# 4_ETHERNET.net
KiCad netlist of a schematic drawn in Altium Designer
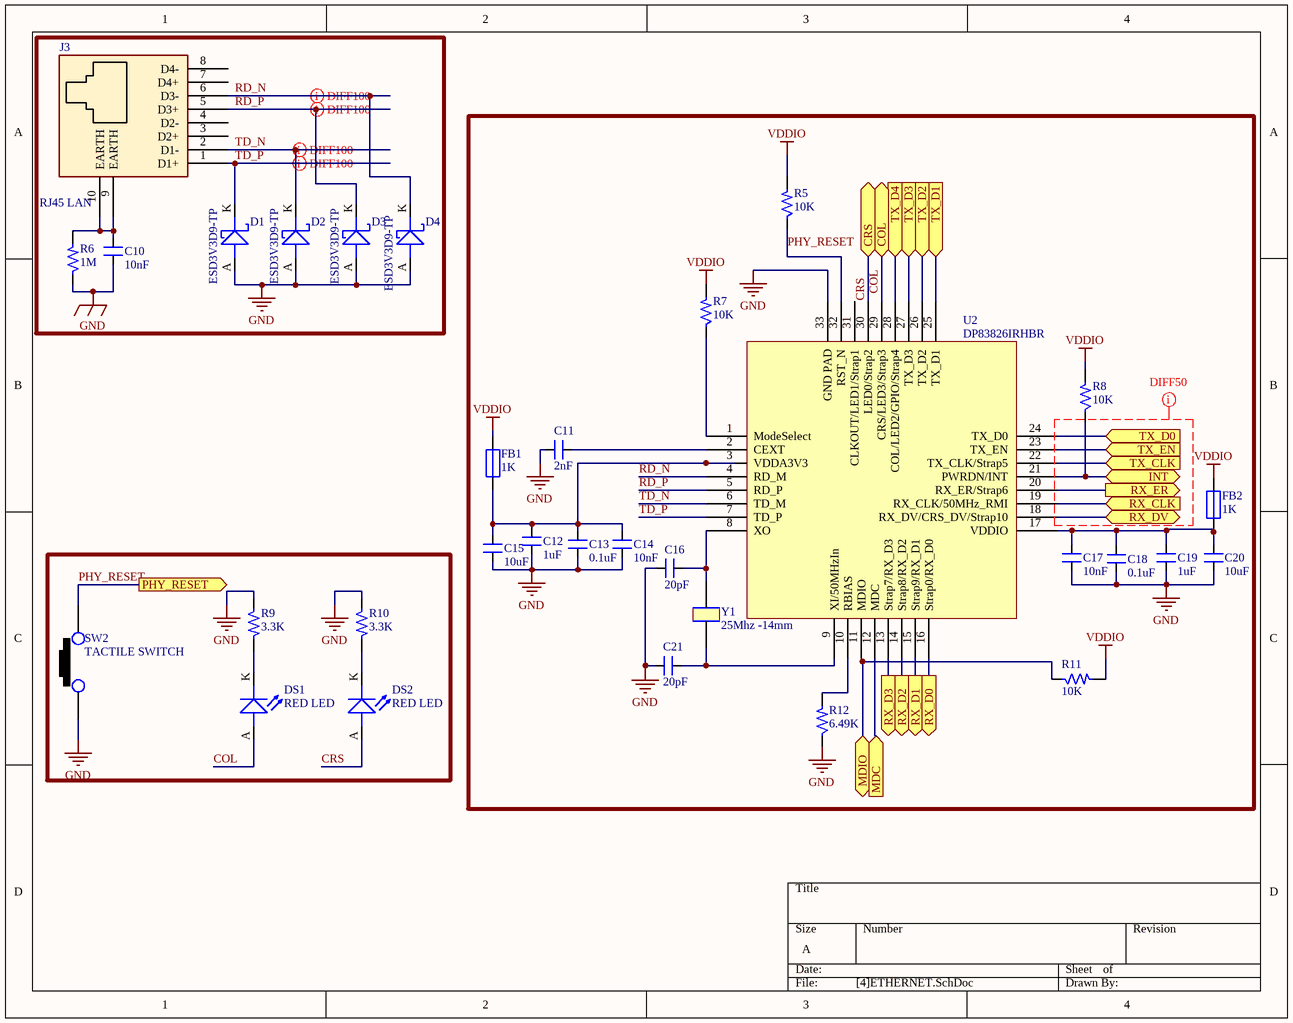
[diagram p0: [4]ETHERNET.SchDoc]

(export (version "E")
  (design (tool "Eeschema 10.0.6"))
  (components
    (comp (ref "C10")
      (value "10nF")
      (footprint "CAP_P196_102X287_H332_RAD_TH")
      (description "10000pF ±10% 1000V (1kV) Ceramic Capacitor X7R Radial")
      (fields
        (field (name "MANUFACTURER") "Yageo")
        (field (name "MANUFACTURER PART NUMBER") "RDER73A103K2K1H03B")
      )
      (libsource (lib "ESTEEMPCBLIB") (part "CAP_10nF-1KV-10%-RAD-TH"))
    )
    (comp (ref "C11")
      (value "2nF")
      (footprint "CAP_0805")
      (description "2000pF ±10% 50V Ceramic Capacitor X7R 0805 (2012 Metric)")
      (fields
        (field (name "MANUFACTURER") "Samsung Electro-Mechanics")
        (field (name "MANUFACTURER PART NUMBER") "CL21B202KBANNNC")
      )
      (libsource (lib "ESTEEMPCBLIB") (part "CAP_2nF-50V-10%-0805"))
    )
    (comp (ref "C12")
      (value "1uF")
      (footprint "CAP_0805")
      (description "1µF ±5% 50V Ceramic Capacitor X7R 0805 (2012 Metric)")
      (fields
        (field (name "MANUFACTURER") "Samsung")
        (field (name "MANUFACTURER PART NUMBER") "CC0805JKX7R9BB105")
      )
      (libsource (lib "ESTEEMPCBLIB") (part "CAP_1uF-50V-5%-0805"))
    )
    (comp (ref "C13")
      (value "0.1uF")
      (footprint "CAP_0805")
      (description "0.1µF ±10% 50V Ceramic Capacitor X7R 0805 (2012 Metric)")
      (fields
        (field (name "MANUFACTURER") "Samsung")
        (field (name "MANUFACTURER PART NUMBER") "CL21B104KBCNNNC")
      )
      (libsource (lib "ESTEEMPCBLIB") (part "CAP_0.1uF-50V-10%-0805"))
    )
    (comp (ref "C14")
      (value "10nF")
      (footprint "CAP_0805")
      (description "10000pF ±10% 50V Ceramic Capacitor X7R 0805 (2012 Metric)")
      (fields
        (field (name "MANUFACTURER") "Samsung")
        (field (name "MANUFACTURER PART NUMBER") "C0805C103K5RECAUTO")
      )
      (libsource (lib "ESTEEMPCBLIB") (part "CAP_10nF-50V-10%-0805"))
    )
    (comp (ref "C15")
      (value "10uF")
      (footprint "CAP_1206")
      (description "10µF ±10% 50V Ceramic Capacitor X7R 1206 (3216 Metric)")
      (fields
        (field (name "MANUFACTURER") "KEMET")
        (field (name "MANUFACTURER PART NUMBER") "CL31B106KBHNNNE")
      )
      (libsource (lib "ESTEEMPCBLIB") (part "CAP_10uF-50V-10%-1206"))
    )
    (comp (ref "C16")
      (value "20pF")
      (footprint "CAP_0805")
      (description "±10% 50V Ceramic Capacitor C0G, NP0 0805 (2012 Metric)")
      (fields
        (field (name "MANUFACTURER") "AVX Corporation")
        (field (name "MANUFACTURER PART NUMBER") "08055A200KAT2A")
      )
      (libsource (lib "ESTEEMPCBLIB") (part "CAP_20pF-50V-10%-0805"))
    )
    (comp (ref "C17")
      (value "10nF")
      (footprint "CAP_0805")
      (description "10000pF ±10% 50V Ceramic Capacitor X7R 0805 (2012 Metric)")
      (fields
        (field (name "MANUFACTURER") "Samsung")
        (field (name "MANUFACTURER PART NUMBER") "C0805C103K5RECAUTO")
      )
      (libsource (lib "ESTEEMPCBLIB") (part "CAP_10nF-50V-10%-0805"))
    )
    (comp (ref "C18")
      (value "0.1uF")
      (footprint "CAP_0805")
      (description "0.1µF ±10% 50V Ceramic Capacitor X7R 0805 (2012 Metric)")
      (fields
        (field (name "MANUFACTURER") "Samsung")
        (field (name "MANUFACTURER PART NUMBER") "CL21B104KBCNNNC")
      )
      (libsource (lib "ESTEEMPCBLIB") (part "CAP_0.1uF-50V-10%-0805"))
    )
    (comp (ref "C19")
      (value "1uF")
      (footprint "CAP_0805")
      (description "1µF ±5% 50V Ceramic Capacitor X7R 0805 (2012 Metric)")
      (fields
        (field (name "MANUFACTURER") "Samsung")
        (field (name "MANUFACTURER PART NUMBER") "CC0805JKX7R9BB105")
      )
      (libsource (lib "ESTEEMPCBLIB") (part "CAP_1uF-50V-5%-0805"))
    )
    (comp (ref "C20")
      (value "10uF")
      (footprint "CAP_1206")
      (description "10µF ±10% 50V Ceramic Capacitor X7R 1206 (3216 Metric)")
      (fields
        (field (name "MANUFACTURER") "KEMET")
        (field (name "MANUFACTURER PART NUMBER") "CL31B106KBHNNNE")
      )
      (libsource (lib "ESTEEMPCBLIB") (part "CAP_10uF-50V-10%-1206"))
    )
    (comp (ref "C21")
      (value "20pF")
      (footprint "CAP_0805")
      (description "±10% 50V Ceramic Capacitor C0G, NP0 0805 (2012 Metric)")
      (fields
        (field (name "MANUFACTURER") "AVX Corporation")
        (field (name "MANUFACTURER PART NUMBER") "08055A200KAT2A")
      )
      (libsource (lib "ESTEEMPCBLIB") (part "CAP_20pF-50V-10%-0805"))
    )
    (comp (ref "D1")
      (value "ESD3V3D9-TP")
      (footprint "DIO_SOD-923")
      (description "8.8V Clamp 5A (8/20µs) Ipp Tvs Diode Surface Mount SOD-923")
      (fields (field (name "MANUFACTURER") "Micro Commercial Co"))
      (libsource (lib "ESTEEMPCBLIB") (part "DIO-T_3.3V-8.8V-SOD923"))
    )
    (comp (ref "D2")
      (value "ESD3V3D9-TP")
      (footprint "DIO_SOD-923")
      (description "8.8V Clamp 5A (8/20µs) Ipp Tvs Diode Surface Mount SOD-923")
      (fields (field (name "MANUFACTURER") "Micro Commercial Co"))
      (libsource (lib "ESTEEMPCBLIB") (part "DIO-T_3.3V-8.8V-SOD923"))
    )
    (comp (ref "D3")
      (value "ESD3V3D9-TP")
      (footprint "DIO_SOD-923")
      (description "8.8V Clamp 5A (8/20µs) Ipp Tvs Diode Surface Mount SOD-923")
      (fields (field (name "MANUFACTURER") "Micro Commercial Co"))
      (libsource (lib "ESTEEMPCBLIB") (part "DIO-T_3.3V-8.8V-SOD923"))
    )
    (comp (ref "D4")
      (value "ESD3V3D9-TP")
      (footprint "DIO_SOD-923")
      (description "8.8V Clamp 5A (8/20µs) Ipp Tvs Diode Surface Mount SOD-923")
      (fields (field (name "MANUFACTURER") "Micro Commercial Co"))
      (libsource (lib "ESTEEMPCBLIB") (part "DIO-T_3.3V-8.8V-SOD923"))
    )
    (comp (ref "DS1")
      (value "RED LED")
      (footprint "LED_0805")
      (description "Red 631nm LED Indication - Discrete 2V 0805 (2012 Metric)")
      (fields
        (field (name "MANUFACTURER") "Vishay Lite-On")
        (field (name "MANUFACTURER PART NUMBER") "LTST-C171KRKT")
      )
      (libsource (lib "ESTEEMPCBLIB") (part "LED_RED-2V-20mA-0805"))
    )
    (comp (ref "DS2")
      (value "RED LED")
      (footprint "LED_0805")
      (description "Red 631nm LED Indication - Discrete 2V 0805 (2012 Metric)")
      (fields
        (field (name "MANUFACTURER") "Vishay Lite-On")
        (field (name "MANUFACTURER PART NUMBER") "LTST-C171KRKT")
      )
      (libsource (lib "ESTEEMPCBLIB") (part "LED_RED-2V-20mA-0805"))
    )
    (comp (ref "FB1")
      (value "1K")
      (footprint "IND_0805")
      (description "1 kOhms @ 100MHz 1 Power Line Ferrite Bead 0805 (2012 Metric) 1.6A")
      (fields
        (field (name "MANUFACTURER") "Laird")
        (field (name "MANUFACTURER PART NUMBER") "BLM21SP102SH1D")
      )
      (libsource (lib "ESTEEMPCBLIB") (part "FB_1K-100MHZ-1.6A-0805"))
    )
    (comp (ref "FB2")
      (value "1K")
      (footprint "IND_0805")
      (description "1 kOhms @ 100MHz 1 Power Line Ferrite Bead 0805 (2012 Metric) 1.6A")
      (fields
        (field (name "MANUFACTURER") "Laird")
        (field (name "MANUFACTURER PART NUMBER") "BLM21SP102SH1D")
      )
      (libsource (lib "ESTEEMPCBLIB") (part "FB_1K-100MHZ-1.6A-0805"))
    )
    (comp (ref "J3")
      (value "RJ45 LAN")
      (footprint "CON10_P106_RJ45_TH_ST")
      (description "8 Pins, 2 Row 2.54mm Pitch, right angle Connector, male")
      (fields
        (field (name "MANUFACTURER") "Assmann")
        (field (name "MANUFACTURER PART NUMBER") "A-2004-2-4-LPS-N-R")
      )
      (libsource (lib "ESTEEMPCBLIB") (part "CON-SKT-RJ_8C8P-RA-TH"))
    )
    (comp (ref "R5")
      (value "10K")
      (footprint "RES_0805")
      (description "10 kOhms ±1% 0.125W, 1/8W Chip Resistor 0805 (2012 Metric) Automotive AEC-Q200 Thick Film")
      (fields (field (name "MANUFACTURER") "CTS") (field (name "MANUFACTURER PART NUMBER") "WR08X1002FTL"))
      (libsource (lib "ESTEEMPCBLIB") (part "RES_10K-0.125W-1%-0805"))
    )
    (comp (ref "R6")
      (value "1M")
      (footprint "RES_0805")
      (description "1 MOhms ±1% 0.125W, 1/8W Chip Resistor 0805 (2012 Metric) Automotive AEC-Q200 Thick Film")
      (fields (field (name "MANUFACTURER") "Walsin") (field (name "MANUFACTURER PART NUMBER") "WR08X1004FTL"))
      (libsource (lib "ESTEEMPCBLIB") (part "RES_1M-0.125W-1%-0805"))
    )
    (comp (ref "R7")
      (value "10K")
      (footprint "RES_0603")
      (description "10 kOhms ±1% 0.1W, 1/10W Chip Resistor 0603 (1608 Metric) Automotive AEC-Q200 Thick Film")
      (fields (field (name "MANUFACTURER") "Walsin") (field (name "MANUFACTURER PART NUMBER") "WR06X1002FTL"))
      (libsource (lib "ESTEEMPCBLIB") (part "RES_10K-0.1W-1%-0603"))
    )
    (comp (ref "R8")
      (value "10K")
      (footprint "RES_0805")
      (description "10 kOhms ±1% 0.125W, 1/8W Chip Resistor 0805 (2012 Metric) Automotive AEC-Q200 Thick Film")
      (fields (field (name "MANUFACTURER") "CTS") (field (name "MANUFACTURER PART NUMBER") "WR08X1002FTL"))
      (libsource (lib "ESTEEMPCBLIB") (part "RES_10K-0.125W-1%-0805"))
    )
    (comp (ref "R9")
      (value "3.3K")
      (footprint "RES_0805")
      (description "3.3 kOhms ±1% 0.125W, 1/8W Chip Resistor 0805 (2012 Metric) Thick Film")
      (fields (field (name "MANUFACTURER") "Panasonic") (field (name "MANUFACTURER PART NUMBER") "1623214-1"))
      (libsource (lib "ESTEEMPCBLIB") (part "RES_3.3K-0.125W-1%-0805"))
    )
    (comp (ref "R10")
      (value "3.3K")
      (footprint "RES_0805")
      (description "3.3 kOhms ±1% 0.125W, 1/8W Chip Resistor 0805 (2012 Metric) Thick Film")
      (fields (field (name "MANUFACTURER") "Panasonic") (field (name "MANUFACTURER PART NUMBER") "1623214-1"))
      (libsource (lib "ESTEEMPCBLIB") (part "RES_3.3K-0.125W-1%-0805"))
    )
    (comp (ref "R11")
      (value "10K")
      (footprint "RES_0805")
      (description "10 kOhms ±1% 0.125W, 1/8W Chip Resistor 0805 (2012 Metric) Automotive AEC-Q200 Thick Film")
      (fields (field (name "MANUFACTURER") "CTS") (field (name "MANUFACTURER PART NUMBER") "WR08X1002FTL"))
      (libsource (lib "ESTEEMPCBLIB") (part "RES_10K-0.125W-1%-0805"))
    )
    (comp (ref "R12")
      (value "6.49K")
      (footprint "RES_0805")
      (description "6.49 kOhms ±1% 0.125W, 1/8W Chip Resistor 0805 (2012 Metric) Moisture Resistant Thick Film")
      (fields
        (field (name "MANUFACTURER") "Stackpole Electronics")
        (field (name "MANUFACTURER PART NUMBER") "RC0805FR-076K49L")
      )
      (libsource (lib "ESTEEMPCBLIB") (part "RES_6.49K-0.125W-1%-0805"))
    )
    (comp (ref "SW2")
      (value "TACTILE SWITCH")
      (footprint "SW_342_SMD")
      (description "Tactile Switch SPST-NO Top Actuated Surface Mount")
      (fields
        (field (name "MANUFACTURER") "ITT C&K")
        (field (name "MANUFACTURER PART NUMBER") "RS-282G05A3-SMRT")
      )
      (libsource (lib "ESTEEMPCBLIB") (part "SW1_RS-282G05A3-SMRT-SMD"))
    )
    (comp (ref "U2")
      (value "DP83826IRHBR")
      (footprint "VQFN32_19_218_23X9_SMD")
      (fields (field (name "MANUFACTURER") "Texas Instruments"))
      (libsource (lib "ESTEEMPCBLIB") (part "IC_DP83826IRHBR"))
    )
    (comp (ref "Y1")
      (value "25Mhz -14mm")
      (footprint "XTAL_314_240X47_SMD")
      (description "25MHz ±30ppm Crystal 20pF 30 Ohms HC-49/US")
      (fields
        (field (name "MANUFACTURER") "Abracon")
        (field (name "MANUFACTURER PART NUMBER") "FOXSDLF/250F-20")
      )
      (libsource (lib "ESTEEMPCBLIB") (part "XTAL_25Mhz-FOXSDLF/250F-20"))
    )
  )
  (nets
    (net (code "1") (name "/COL") (class "Default")
      (node (ref "DS1") (pin "A") (pinfunction "ANODE_A") (pintype "passive"))
      (node (ref "U2") (pin "29") (pinfunction "CRS/LED3/Strap3_29") (pintype "passive"))
    )
    (net (code "2") (name "/CRS") (class "Default")
      (node (ref "DS2") (pin "A") (pinfunction "ANODE_A") (pintype "passive"))
      (node (ref "U2") (pin "30") (pinfunction "LED0/Strap2_30") (pintype "passive"))
    )
    (net (code "3") (name "/INT") (class "Default")
      (node (ref "R8") (pin "1") (pinfunction "1_1") (pintype "passive"))
      (node (ref "U2") (pin "21") (pinfunction "PWRDN/INT_21") (pintype "passive"))
    )
    (net (code "4") (name "/MDC") (class "Default")
      (node (ref "U2") (pin "12") (pinfunction "MDC_12") (pintype "passive"))
    )
    (net (code "5") (name "/MDIO") (class "Default")
      (node (ref "R11") (pin "1") (pinfunction "1_1") (pintype "passive"))
      (node (ref "U2") (pin "11") (pinfunction "MDIO_11") (pintype "passive"))
    )
    (net (code "6") (name "/PHY_RESET") (class "Default")
      (node (ref "R5") (pin "1") (pinfunction "1_1") (pintype "passive"))
      (node (ref "SW2") (pin "2") (pinfunction "2_2") (pintype "passive"))
      (node (ref "U2") (pin "32") (pinfunction "RST_N_32") (pintype "passive"))
    )
    (net (code "7") (name "/RD_N") (class "Default")
      (node (ref "D4") (pin "K") (pinfunction "K_K") (pintype "passive"))
      (node (ref "J3") (pin "6") (pinfunction "D3-_6") (pintype "passive"))
      (node (ref "U2") (pin "4") (pinfunction "RD_M_4") (pintype "passive"))
    )
    (net (code "8") (name "/RD_P") (class "Default")
      (node (ref "D3") (pin "K") (pinfunction "K_K") (pintype "passive"))
      (node (ref "J3") (pin "5") (pinfunction "D3+_5") (pintype "passive"))
      (node (ref "U2") (pin "5") (pinfunction "RD_P_5") (pintype "passive"))
    )
    (net (code "9") (name "/RX_CLK") (class "Default")
      (node (ref "U2") (pin "19") (pinfunction "RX_CLK/50MHz_RMI_19") (pintype "passive"))
    )
    (net (code "10") (name "/RX_D0") (class "Default")
      (node (ref "U2") (pin "16") (pinfunction "Strap0/RX_D0_16") (pintype "passive"))
    )
    (net (code "11") (name "/RX_D1") (class "Default")
      (node (ref "U2") (pin "15") (pinfunction "Strap9/RX_D1_15") (pintype "passive"))
    )
    (net (code "12") (name "/RX_D2") (class "Default")
      (node (ref "U2") (pin "14") (pinfunction "Strap8/RX_D2_14") (pintype "passive"))
    )
    (net (code "13") (name "/RX_D3") (class "Default")
      (node (ref "U2") (pin "13") (pinfunction "Strap7/RX_D3_13") (pintype "passive"))
    )
    (net (code "14") (name "/RX_DV") (class "Default")
      (node (ref "U2") (pin "18") (pinfunction "RX_DV/CRS_DV/Strap10_18") (pintype "passive"))
    )
    (net (code "15") (name "/RX_ER") (class "Default")
      (node (ref "U2") (pin "20") (pinfunction "RX_ER/Strap6_20") (pintype "passive"))
    )
    (net (code "16") (name "/TD_N") (class "Default")
      (node (ref "D2") (pin "K") (pinfunction "K_K") (pintype "passive"))
      (node (ref "J3") (pin "2") (pinfunction "D1-_2") (pintype "passive"))
      (node (ref "U2") (pin "6") (pinfunction "TD_M_6") (pintype "passive"))
    )
    (net (code "17") (name "/TD_P") (class "Default")
      (node (ref "D1") (pin "K") (pinfunction "K_K") (pintype "passive"))
      (node (ref "J3") (pin "1") (pinfunction "D1+_1") (pintype "passive"))
      (node (ref "U2") (pin "7") (pinfunction "TD_P_7") (pintype "passive"))
    )
    (net (code "18") (name "/TX_CLK") (class "Default")
      (node (ref "U2") (pin "22") (pinfunction "TX_CLK/Strap5_22") (pintype "passive"))
    )
    (net (code "19") (name "/TX_D0") (class "Default")
      (node (ref "U2") (pin "24") (pinfunction "TX_D0_24") (pintype "passive"))
    )
    (net (code "20") (name "/TX_D1") (class "Default")
      (node (ref "U2") (pin "25") (pinfunction "TX_D1_25") (pintype "passive"))
    )
    (net (code "21") (name "/TX_D2") (class "Default")
      (node (ref "U2") (pin "26") (pinfunction "TX_D2_26") (pintype "passive"))
    )
    (net (code "22") (name "/TX_D3") (class "Default")
      (node (ref "U2") (pin "27") (pinfunction "TX_D3_27") (pintype "passive"))
    )
    (net (code "23") (name "/TX_D4") (class "Default")
      (node (ref "U2") (pin "28") (pinfunction "COL/LED2/GPIO/Strap4_28") (pintype "passive"))
    )
    (net (code "24") (name "/TX_EN") (class "Default")
      (node (ref "U2") (pin "23") (pinfunction "TX_EN_23") (pintype "passive"))
    )
    (net (code "25") (name "GND") (class "Default")
      (node (ref "C10") (pin "1") (pinfunction "1_1") (pintype "passive"))
      (node (ref "C11") (pin "1") (pinfunction "1_1") (pintype "passive"))
      (node (ref "C12") (pin "1") (pinfunction "1_1") (pintype "passive"))
      (node (ref "C13") (pin "1") (pinfunction "1_1") (pintype "passive"))
      (node (ref "C14") (pin "1") (pinfunction "1_1") (pintype "passive"))
      (node (ref "C15") (pin "1") (pinfunction "1_1") (pintype "passive"))
      (node (ref "C16") (pin "1") (pinfunction "1_1") (pintype "passive"))
      (node (ref "C17") (pin "1") (pinfunction "1_1") (pintype "passive"))
      (node (ref "C18") (pin "1") (pinfunction "1_1") (pintype "passive"))
      (node (ref "C19") (pin "1") (pinfunction "1_1") (pintype "passive"))
      (node (ref "C20") (pin "1") (pinfunction "1_1") (pintype "passive"))
      (node (ref "C21") (pin "1") (pinfunction "1_1") (pintype "passive"))
      (node (ref "D1") (pin "A") (pinfunction "A_A") (pintype "passive"))
      (node (ref "D2") (pin "A") (pinfunction "A_A") (pintype "passive"))
      (node (ref "D3") (pin "A") (pinfunction "A_A") (pintype "passive"))
      (node (ref "D4") (pin "A") (pinfunction "A_A") (pintype "passive"))
      (node (ref "R10") (pin "1") (pinfunction "1_1") (pintype "passive"))
      (node (ref "R12") (pin "1") (pinfunction "1_1") (pintype "passive"))
      (node (ref "R6") (pin "1") (pinfunction "1_1") (pintype "passive"))
      (node (ref "R9") (pin "1") (pinfunction "1_1") (pintype "passive"))
      (node (ref "SW2") (pin "1") (pinfunction "1_1") (pintype "passive"))
      (node (ref "U2") (pin "33") (pinfunction "GND_PAD_33") (pintype "passive"))
    )
    (net (code "26") (name "Net-(C10-Pad2)") (class "Default")
      (node (ref "C10") (pin "2") (pinfunction "2_2") (pintype "passive"))
      (node (ref "J3") (pin "10") (pinfunction "EARTH_10") (pintype "passive"))
      (node (ref "J3") (pin "9") (pinfunction "EARTH_9") (pintype "passive"))
      (node (ref "R6") (pin "2") (pinfunction "2_2") (pintype "passive"))
    )
    (net (code "27") (name "Net-(DS1-CATHODE)") (class "Default")
      (node (ref "DS1") (pin "K") (pinfunction "CATHODE_K") (pintype "passive"))
      (node (ref "R9") (pin "2") (pinfunction "2_2") (pintype "passive"))
    )
    (net (code "28") (name "Net-(DS2-CATHODE)") (class "Default")
      (node (ref "DS2") (pin "K") (pinfunction "CATHODE_K") (pintype "passive"))
      (node (ref "R10") (pin "2") (pinfunction "2_2") (pintype "passive"))
    )
    (net (code "29") (name "Net-(U2-CEXT)") (class "Default")
      (node (ref "C11") (pin "2") (pinfunction "2_2") (pintype "passive"))
      (node (ref "U2") (pin "2") (pinfunction "CEXT_2") (pintype "passive"))
    )
    (net (code "30") (name "Net-(U2-ModeSelect)") (class "Default")
      (node (ref "R7") (pin "1") (pinfunction "1_1") (pintype "passive"))
      (node (ref "U2") (pin "1") (pinfunction "ModeSelect_1") (pintype "passive"))
    )
    (net (code "31") (name "Net-(U2-RBIAS)") (class "Default")
      (node (ref "R12") (pin "2") (pinfunction "2_2") (pintype "passive"))
      (node (ref "U2") (pin "10") (pinfunction "RBIAS_10") (pintype "passive"))
    )
    (net (code "32") (name "Net-(U2-VDDA3V3)") (class "Default")
      (node (ref "C12") (pin "2") (pinfunction "2_2") (pintype "passive"))
      (node (ref "C13") (pin "2") (pinfunction "2_2") (pintype "passive"))
      (node (ref "C14") (pin "2") (pinfunction "2_2") (pintype "passive"))
      (node (ref "C15") (pin "2") (pinfunction "2_2") (pintype "passive"))
      (node (ref "FB1") (pin "1") (pinfunction "1_1") (pintype "passive"))
      (node (ref "U2") (pin "3") (pinfunction "VDDA3V3_3") (pintype "passive"))
    )
    (net (code "33") (name "Net-(U2-VDDIO)") (class "Default")
      (node (ref "C17") (pin "2") (pinfunction "2_2") (pintype "passive"))
      (node (ref "C18") (pin "2") (pinfunction "2_2") (pintype "passive"))
      (node (ref "C19") (pin "2") (pinfunction "2_2") (pintype "passive"))
      (node (ref "C20") (pin "2") (pinfunction "2_2") (pintype "passive"))
      (node (ref "FB2") (pin "1") (pinfunction "1_1") (pintype "passive"))
      (node (ref "U2") (pin "17") (pinfunction "VDDIO_17") (pintype "passive"))
    )
    (net (code "34") (name "Net-(U2-XI{slash}50MHzIn)") (class "Default")
      (node (ref "C21") (pin "2") (pinfunction "2_2") (pintype "passive"))
      (node (ref "U2") (pin "9") (pinfunction "XI/50MHzIn_9") (pintype "passive"))
      (node (ref "Y1") (pin "1") (pinfunction "1_1") (pintype "passive"))
    )
    (net (code "35") (name "Net-(U2-XO)") (class "Default")
      (node (ref "C16") (pin "2") (pinfunction "2_2") (pintype "passive"))
      (node (ref "U2") (pin "8") (pinfunction "XO_8") (pintype "passive"))
      (node (ref "Y1") (pin "2") (pinfunction "2_2") (pintype "passive"))
    )
    (net (code "36") (name "VDDIO") (class "Default")
      (node (ref "FB1") (pin "2") (pinfunction "2_2") (pintype "passive"))
      (node (ref "FB2") (pin "2") (pinfunction "2_2") (pintype "passive"))
      (node (ref "R11") (pin "2") (pinfunction "2_2") (pintype "passive"))
      (node (ref "R5") (pin "2") (pinfunction "2_2") (pintype "passive"))
      (node (ref "R7") (pin "2") (pinfunction "2_2") (pintype "passive"))
      (node (ref "R8") (pin "2") (pinfunction "2_2") (pintype "passive"))
    )
    (net (code "37") (name "unconnected-(J3-D2+-Pad3)") (class "Default")
      (node (ref "J3") (pin "3") (pinfunction "D2+_3") (pintype "passive"))
    )
    (net (code "38") (name "unconnected-(J3-D2--Pad4)") (class "Default")
      (node (ref "J3") (pin "4") (pinfunction "D2-_4") (pintype "passive"))
    )
    (net (code "39") (name "unconnected-(J3-D4+-Pad7)") (class "Default")
      (node (ref "J3") (pin "7") (pinfunction "D4+_7") (pintype "passive"))
    )
    (net (code "40") (name "unconnected-(J3-D4--Pad8)") (class "Default")
      (node (ref "J3") (pin "8") (pinfunction "D4-_8") (pintype "passive"))
    )
    (net (code "41") (name "unconnected-(U2-CLKOUT{slash}LED1{slash}Strap1-Pad31)") (class "Default")
      (node (ref "U2") (pin "31") (pinfunction "CLKOUT/LED1/Strap1_31") (pintype "passive"))
    )
  )
)
